# ReuseBlock_Cockcrof_Walton_PCB_2025-01-0.net
KiCad netlist of a schematic drawn in EasyEDA Pro
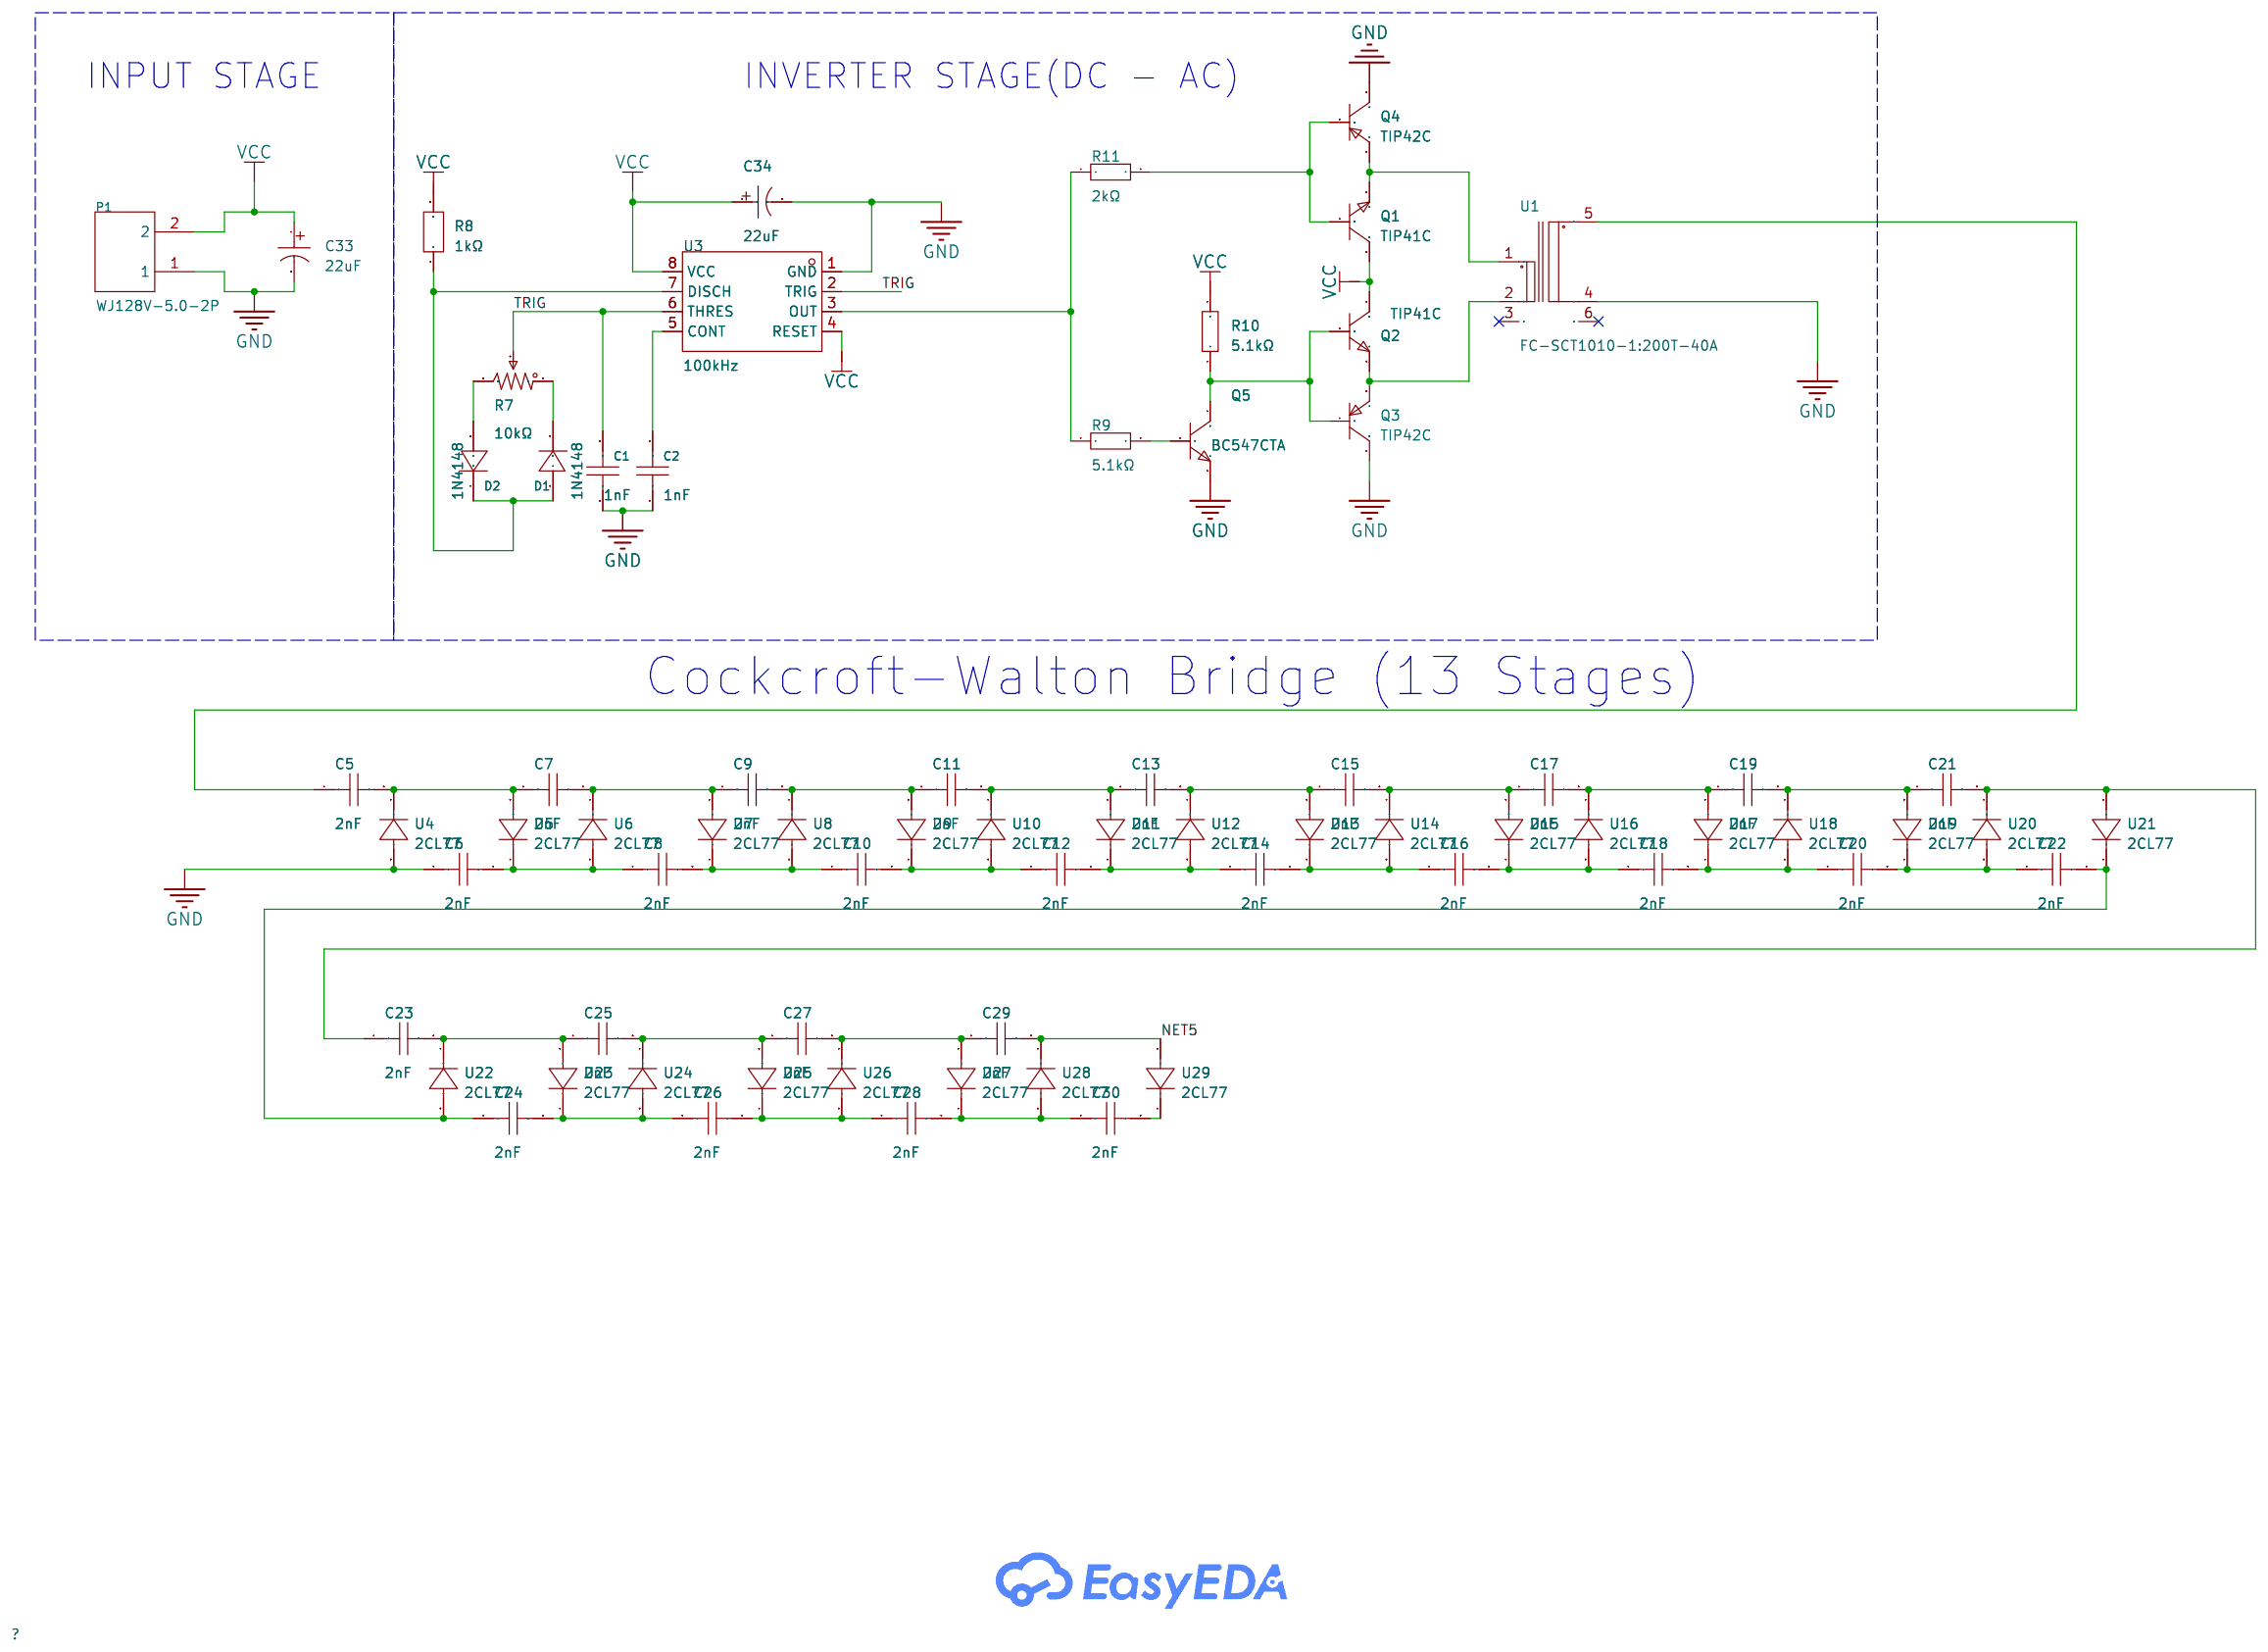
[diagram p0: schematic sheet]

(export (version "E")
  (design (tool "Eeschema 10.0.6"))
  (components
    (comp (ref "C1")
      (value "1nF")
      (footprint "easyedapro:CAP-TH_L8.0-W3.0-P5.0-D0.60")
      (fields (field (name "Manufacturer Part") "R08B1B102KN0B0S0N0") (field (name "Manufacturer") "STE(松田)"))
      (libsource (lib "easyedapro") (part "R08B1B102KN0B0S0N0"))
    )
    (comp (ref "C2")
      (value "1nF")
      (footprint "easyedapro:CAP-TH_L8.0-W3.0-P5.0-D0.60")
      (fields (field (name "Manufacturer Part") "R08B1B102KN0B0S0N0") (field (name "Manufacturer") "STE(松田)"))
      (libsource (lib "easyedapro") (part "R08B1B102KN0B0S0N0"))
    )
    (comp (ref "C5")
      (value "2nF")
      (footprint "easyedapro:CAP-TH_L19.0-W8.0-P12.50-D0.8-S8.0")
      (fields
        (field (name "Manufacturer Part") "HVCC153Y6P202MEAX")
        (field (name "Manufacturer") "VISHAY(威世)")
      )
      (libsource (lib "easyedapro") (part "HVCC153Y6P202MEAX"))
    )
    (comp (ref "C6")
      (value "2nF")
      (footprint "easyedapro:CAP-TH_L19.0-W8.0-P12.50-D0.8-S8.0")
      (fields
        (field (name "Manufacturer Part") "HVCC153Y6P202MEAX")
        (field (name "Manufacturer") "VISHAY(威世)")
      )
      (libsource (lib "easyedapro") (part "HVCC153Y6P202MEAX"))
    )
    (comp (ref "C7")
      (value "2nF")
      (footprint "easyedapro:CAP-TH_L19.0-W8.0-P12.50-D0.8-S8.0")
      (fields
        (field (name "Manufacturer Part") "HVCC153Y6P202MEAX")
        (field (name "Manufacturer") "VISHAY(威世)")
      )
      (libsource (lib "easyedapro") (part "HVCC153Y6P202MEAX"))
    )
    (comp (ref "C8")
      (value "2nF")
      (footprint "easyedapro:CAP-TH_L19.0-W8.0-P12.50-D0.8-S8.0")
      (fields
        (field (name "Manufacturer Part") "HVCC153Y6P202MEAX")
        (field (name "Manufacturer") "VISHAY(威世)")
      )
      (libsource (lib "easyedapro") (part "HVCC153Y6P202MEAX"))
    )
    (comp (ref "C9")
      (value "2nF")
      (footprint "easyedapro:CAP-TH_L19.0-W8.0-P12.50-D0.8-S8.0")
      (fields
        (field (name "Manufacturer Part") "HVCC153Y6P202MEAX")
        (field (name "Manufacturer") "VISHAY(威世)")
      )
      (libsource (lib "easyedapro") (part "HVCC153Y6P202MEAX"))
    )
    (comp (ref "C10")
      (value "2nF")
      (footprint "easyedapro:CAP-TH_L19.0-W8.0-P12.50-D0.8-S8.0")
      (fields
        (field (name "Manufacturer Part") "HVCC153Y6P202MEAX")
        (field (name "Manufacturer") "VISHAY(威世)")
      )
      (libsource (lib "easyedapro") (part "HVCC153Y6P202MEAX"))
    )
    (comp (ref "C11")
      (value "2nF")
      (footprint "easyedapro:CAP-TH_L19.0-W8.0-P12.50-D0.8-S8.0")
      (fields
        (field (name "Manufacturer Part") "HVCC153Y6P202MEAX")
        (field (name "Manufacturer") "VISHAY(威世)")
      )
      (libsource (lib "easyedapro") (part "HVCC153Y6P202MEAX"))
    )
    (comp (ref "C12")
      (value "2nF")
      (footprint "easyedapro:CAP-TH_L19.0-W8.0-P12.50-D0.8-S8.0")
      (fields
        (field (name "Manufacturer Part") "HVCC153Y6P202MEAX")
        (field (name "Manufacturer") "VISHAY(威世)")
      )
      (libsource (lib "easyedapro") (part "HVCC153Y6P202MEAX"))
    )
    (comp (ref "C13")
      (value "2nF")
      (footprint "easyedapro:CAP-TH_L19.0-W8.0-P12.50-D0.8-S8.0")
      (fields
        (field (name "Manufacturer Part") "HVCC153Y6P202MEAX")
        (field (name "Manufacturer") "VISHAY(威世)")
      )
      (libsource (lib "easyedapro") (part "HVCC153Y6P202MEAX"))
    )
    (comp (ref "C14")
      (value "2nF")
      (footprint "easyedapro:CAP-TH_L19.0-W8.0-P12.50-D0.8-S8.0")
      (fields
        (field (name "Manufacturer Part") "HVCC153Y6P202MEAX")
        (field (name "Manufacturer") "VISHAY(威世)")
      )
      (libsource (lib "easyedapro") (part "HVCC153Y6P202MEAX"))
    )
    (comp (ref "C15")
      (value "2nF")
      (footprint "easyedapro:CAP-TH_L19.0-W8.0-P12.50-D0.8-S8.0")
      (fields
        (field (name "Manufacturer Part") "HVCC153Y6P202MEAX")
        (field (name "Manufacturer") "VISHAY(威世)")
      )
      (libsource (lib "easyedapro") (part "HVCC153Y6P202MEAX"))
    )
    (comp (ref "C16")
      (value "2nF")
      (footprint "easyedapro:CAP-TH_L19.0-W8.0-P12.50-D0.8-S8.0")
      (fields
        (field (name "Manufacturer Part") "HVCC153Y6P202MEAX")
        (field (name "Manufacturer") "VISHAY(威世)")
      )
      (libsource (lib "easyedapro") (part "HVCC153Y6P202MEAX"))
    )
    (comp (ref "C17")
      (value "2nF")
      (footprint "easyedapro:CAP-TH_L19.0-W8.0-P12.50-D0.8-S8.0")
      (fields
        (field (name "Manufacturer Part") "HVCC153Y6P202MEAX")
        (field (name "Manufacturer") "VISHAY(威世)")
      )
      (libsource (lib "easyedapro") (part "HVCC153Y6P202MEAX"))
    )
    (comp (ref "C18")
      (value "2nF")
      (footprint "easyedapro:CAP-TH_L19.0-W8.0-P12.50-D0.8-S8.0")
      (fields
        (field (name "Manufacturer Part") "HVCC153Y6P202MEAX")
        (field (name "Manufacturer") "VISHAY(威世)")
      )
      (libsource (lib "easyedapro") (part "HVCC153Y6P202MEAX"))
    )
    (comp (ref "C19")
      (value "2nF")
      (footprint "easyedapro:CAP-TH_L19.0-W8.0-P12.50-D0.8-S8.0")
      (fields
        (field (name "Manufacturer Part") "HVCC153Y6P202MEAX")
        (field (name "Manufacturer") "VISHAY(威世)")
      )
      (libsource (lib "easyedapro") (part "HVCC153Y6P202MEAX"))
    )
    (comp (ref "C20")
      (value "2nF")
      (footprint "easyedapro:CAP-TH_L19.0-W8.0-P12.50-D0.8-S8.0")
      (fields
        (field (name "Manufacturer Part") "HVCC153Y6P202MEAX")
        (field (name "Manufacturer") "VISHAY(威世)")
      )
      (libsource (lib "easyedapro") (part "HVCC153Y6P202MEAX"))
    )
    (comp (ref "C21")
      (value "2nF")
      (footprint "easyedapro:CAP-TH_L19.0-W8.0-P12.50-D0.8-S8.0")
      (fields
        (field (name "Manufacturer Part") "HVCC153Y6P202MEAX")
        (field (name "Manufacturer") "VISHAY(威世)")
      )
      (libsource (lib "easyedapro") (part "HVCC153Y6P202MEAX"))
    )
    (comp (ref "C22")
      (value "2nF")
      (footprint "easyedapro:CAP-TH_L19.0-W8.0-P12.50-D0.8-S8.0")
      (fields
        (field (name "Manufacturer Part") "HVCC153Y6P202MEAX")
        (field (name "Manufacturer") "VISHAY(威世)")
      )
      (libsource (lib "easyedapro") (part "HVCC153Y6P202MEAX"))
    )
    (comp (ref "C23")
      (value "2nF")
      (footprint "easyedapro:CAP-TH_L19.0-W8.0-P12.50-D0.8-S8.0")
      (fields
        (field (name "Manufacturer Part") "HVCC153Y6P202MEAX")
        (field (name "Manufacturer") "VISHAY(威世)")
      )
      (libsource (lib "easyedapro") (part "HVCC153Y6P202MEAX"))
    )
    (comp (ref "C24")
      (value "2nF")
      (footprint "easyedapro:CAP-TH_L19.0-W8.0-P12.50-D0.8-S8.0")
      (fields
        (field (name "Manufacturer Part") "HVCC153Y6P202MEAX")
        (field (name "Manufacturer") "VISHAY(威世)")
      )
      (libsource (lib "easyedapro") (part "HVCC153Y6P202MEAX"))
    )
    (comp (ref "C25")
      (value "2nF")
      (footprint "easyedapro:CAP-TH_L19.0-W8.0-P12.50-D0.8-S8.0")
      (fields
        (field (name "Manufacturer Part") "HVCC153Y6P202MEAX")
        (field (name "Manufacturer") "VISHAY(威世)")
      )
      (libsource (lib "easyedapro") (part "HVCC153Y6P202MEAX"))
    )
    (comp (ref "C26")
      (value "2nF")
      (footprint "easyedapro:CAP-TH_L19.0-W8.0-P12.50-D0.8-S8.0")
      (fields
        (field (name "Manufacturer Part") "HVCC153Y6P202MEAX")
        (field (name "Manufacturer") "VISHAY(威世)")
      )
      (libsource (lib "easyedapro") (part "HVCC153Y6P202MEAX"))
    )
    (comp (ref "C27")
      (value "2nF")
      (footprint "easyedapro:CAP-TH_L19.0-W8.0-P12.50-D0.8-S8.0")
      (fields
        (field (name "Manufacturer Part") "HVCC153Y6P202MEAX")
        (field (name "Manufacturer") "VISHAY(威世)")
      )
      (libsource (lib "easyedapro") (part "HVCC153Y6P202MEAX"))
    )
    (comp (ref "C28")
      (value "2nF")
      (footprint "easyedapro:CAP-TH_L19.0-W8.0-P12.50-D0.8-S8.0")
      (fields
        (field (name "Manufacturer Part") "HVCC153Y6P202MEAX")
        (field (name "Manufacturer") "VISHAY(威世)")
      )
      (libsource (lib "easyedapro") (part "HVCC153Y6P202MEAX"))
    )
    (comp (ref "C29")
      (value "2nF")
      (footprint "easyedapro:CAP-TH_L19.0-W8.0-P12.50-D0.8-S8.0")
      (fields
        (field (name "Manufacturer Part") "HVCC153Y6P202MEAX")
        (field (name "Manufacturer") "VISHAY(威世)")
      )
      (libsource (lib "easyedapro") (part "HVCC153Y6P202MEAX"))
    )
    (comp (ref "C30")
      (value "2nF")
      (footprint "easyedapro:CAP-TH_L19.0-W8.0-P12.50-D0.8-S8.0")
      (fields
        (field (name "Manufacturer Part") "HVCC153Y6P202MEAX")
        (field (name "Manufacturer") "VISHAY(威世)")
      )
      (libsource (lib "easyedapro") (part "HVCC153Y6P202MEAX"))
    )
    (comp (ref "C33")
      (value "22uF")
      (footprint "easyedapro:CAP-TH_BD5.0-P2.00-D0.8-FD")
      (fields
        (field (name "Manufacturer Part") "GR226M050D11RR0VH4FP0")
        (field (name "Manufacturer") "CX(承兴)")
      )
      (libsource (lib "easyedapro") (part "22UF 50V高频低阻"))
    )
    (comp (ref "C34")
      (value "22uF")
      (footprint "easyedapro:CAP-TH_BD5.0-P2.00-D0.8-FD")
      (fields
        (field (name "Manufacturer Part") "GR226M050D11RR0VH4FP0")
        (field (name "Manufacturer") "CX(承兴)")
      )
      (libsource (lib "easyedapro") (part "22UF 50V高频低阻"))
    )
    (comp (ref "D1")
      (value "1N4148")
      (footprint "easyedapro:DO-35_BD2.0-L4.2-P8.20-D0.5-RD")
      (fields (field (name "Manufacturer") "LGE(鲁光)"))
      (libsource (lib "easyedapro") (part "1N4148_C402212"))
    )
    (comp (ref "D2")
      (value "1N4148")
      (footprint "easyedapro:DO-35_BD2.0-L4.2-P8.20-D0.5-RD")
      (fields (field (name "Manufacturer") "LGE(鲁光)"))
      (libsource (lib "easyedapro") (part "1N4148_C402212"))
    )
    (comp (ref "P1")
      (value "WJ128V-5.0-2P")
      (footprint "easyedapro:CONN-TH_2P-P5.00_WJ128V-5.0-2P")
      (fields (field (name "Manufacturer") "KANGNEX(康奈克斯电气)"))
      (libsource (lib "easyedapro") (part "WJ128V-5.0-2P"))
    )
    (comp (ref "Q1")
      (value "TIP41C")
      (footprint "easyedapro:TO-220-3_L10.0-W4.5-P2.54-T")
      (fields (field (name "Manufacturer") "CJ(江苏长电/长晶)"))
      (libsource (lib "easyedapro") (part "TIP41C"))
    )
    (comp (ref "Q2")
      (value "TIP41C")
      (footprint "easyedapro:TO-220-3_L10.0-W4.5-P2.54-T")
      (fields (field (name "Manufacturer") "CJ(江苏长电/长晶)"))
      (libsource (lib "easyedapro") (part "TIP41C"))
    )
    (comp (ref "Q3")
      (value "TIP42C")
      (footprint "easyedapro:ITO-220AB-3_L10.2-W4.5-P2.60-L")
      (fields (field (name "Manufacturer") "ST(意法半导体)"))
      (libsource (lib "easyedapro") (part "TIP42C_C410524"))
    )
    (comp (ref "Q4")
      (value "TIP42C")
      (footprint "easyedapro:ITO-220AB-3_L10.2-W4.5-P2.60-L")
      (fields (field (name "Manufacturer") "ST(意法半导体)"))
      (libsource (lib "easyedapro") (part "TIP42C_C410524"))
    )
    (comp (ref "Q5")
      (value "BC547CTA")
      (footprint "easyedapro:TO-92-3_L4.8-W3.7-P2.54-L")
      (fields (field (name "Manufacturer") "onsemi(安森美)"))
      (libsource (lib "easyedapro") (part "BC547CTA"))
    )
    (comp (ref "R7")
      (value "10kΩ")
      (footprint "easyedapro:RES-ADJ-TH_3P-L10.0-W10.0-P2.50-L")
      (description "Resistance: Tolerance:±10% Tolerance:±10%")
      (fields (field (name "Manufacturer Part") "3296W-1-103") (field (name "Manufacturer") "BOCHEN(博晨)"))
      (libsource (lib "easyedapro") (part "3296W-1-103"))
    )
    (comp (ref "R8")
      (value "1kΩ")
      (footprint "easyedapro:RES-TH_BD2.3-L6.5-P10.50-D0.5")
      (fields (field (name "Manufacturer Part") "MF1/4W-1KΩ±1%T52") (field (name "Manufacturer") "华星机电"))
      (libsource (lib "easyedapro") (part "MF1/4W-1KΩ±1%T52"))
    )
    (comp (ref "R9")
      (value "5.1kΩ")
      (footprint "easyedapro:RES-TH_BD2.2-L6.5-P10.50-D0.6")
      (fields
        (field (name "Manufacturer Part") "CFR0W4J0512A50")
        (field (name "Manufacturer") "UNI-ROYAL(厚声)")
      )
      (libsource (lib "easyedapro") (part "CFR0W4J0512A50"))
    )
    (comp (ref "R10")
      (value "5.1kΩ")
      (footprint "easyedapro:RES-TH_BD2.2-L6.5-P10.50-D0.6")
      (fields
        (field (name "Manufacturer Part") "CFR0W4J0512A50")
        (field (name "Manufacturer") "UNI-ROYAL(厚声)")
      )
      (libsource (lib "easyedapro") (part "CFR0W4J0512A50"))
    )
    (comp (ref "R11")
      (value "2kΩ")
      (footprint "easyedapro:RES-TH_BD2.2-L6.5-P10.50-D0.6")
      (fields
        (field (name "Manufacturer Part") "MFR0W4F2001A50")
        (field (name "Manufacturer") "UNI-ROYAL(厚声)")
      )
      (libsource (lib "easyedapro") (part "MFR0W4F2001A50"))
    )
    (comp (ref "U1")
      (value "FC-SCT1010-1:200T-40A")
      (footprint "easyedapro:XFMR-SMD_6P-P2.50_FC-SCT1010")
      (description "Current Ratio:1:200 Current Rating:40A")
      (fields (field (name "Manufacturer") "FC(方成)"))
      (libsource (lib "easyedapro") (part "FC-SCT1010-1{colon}200T-40A"))
    )
    (comp (ref "U3")
      (value "100kHz")
      (footprint "easyedapro:DIP-8_L9.8-W6.6-P2.54-LS7.6-BL")
      (fields (field (name "Manufacturer Part") "NE555P") (field (name "Manufacturer") "TI(德州仪器)"))
      (libsource (lib "easyedapro") (part "NE555P"))
    )
    (comp (ref "U4")
      (value "2CL77")
      (footprint "easyedapro:DIO-TH_BD3.0-L12.0-P16.00-D0.6")
      (description "Reverse Voltage (Vr): Average Rectified Current (Io): Reverse Leakage Current:2uA")
      (fields (field (name "Manufacturer") "SUNMATE(森美特)"))
      (libsource (lib "easyedapro") (part "2CL77"))
    )
    (comp (ref "U5")
      (value "2CL77")
      (footprint "easyedapro:DIO-TH_BD3.0-L12.0-P16.00-D0.6")
      (description "Reverse Voltage (Vr): Average Rectified Current (Io): Reverse Leakage Current:2uA")
      (fields (field (name "Manufacturer") "SUNMATE(森美特)"))
      (libsource (lib "easyedapro") (part "2CL77"))
    )
    (comp (ref "U6")
      (value "2CL77")
      (footprint "easyedapro:DIO-TH_BD3.0-L12.0-P16.00-D0.6")
      (description "Reverse Voltage (Vr): Average Rectified Current (Io): Reverse Leakage Current:2uA")
      (fields (field (name "Manufacturer") "SUNMATE(森美特)"))
      (libsource (lib "easyedapro") (part "2CL77"))
    )
    (comp (ref "U7")
      (value "2CL77")
      (footprint "easyedapro:DIO-TH_BD3.0-L12.0-P16.00-D0.6")
      (description "Reverse Voltage (Vr): Average Rectified Current (Io): Reverse Leakage Current:2uA")
      (fields (field (name "Manufacturer") "SUNMATE(森美特)"))
      (libsource (lib "easyedapro") (part "2CL77"))
    )
    (comp (ref "U8")
      (value "2CL77")
      (footprint "easyedapro:DIO-TH_BD3.0-L12.0-P16.00-D0.6")
      (description "Reverse Voltage (Vr): Average Rectified Current (Io): Reverse Leakage Current:2uA")
      (fields (field (name "Manufacturer") "SUNMATE(森美特)"))
      (libsource (lib "easyedapro") (part "2CL77"))
    )
    (comp (ref "U9")
      (value "2CL77")
      (footprint "easyedapro:DIO-TH_BD3.0-L12.0-P16.00-D0.6")
      (description "Reverse Voltage (Vr): Average Rectified Current (Io): Reverse Leakage Current:2uA")
      (fields (field (name "Manufacturer") "SUNMATE(森美特)"))
      (libsource (lib "easyedapro") (part "2CL77"))
    )
    (comp (ref "U10")
      (value "2CL77")
      (footprint "easyedapro:DIO-TH_BD3.0-L12.0-P16.00-D0.6")
      (description "Reverse Voltage (Vr): Average Rectified Current (Io): Reverse Leakage Current:2uA")
      (fields (field (name "Manufacturer") "SUNMATE(森美特)"))
      (libsource (lib "easyedapro") (part "2CL77"))
    )
    (comp (ref "U11")
      (value "2CL77")
      (footprint "easyedapro:DIO-TH_BD3.0-L12.0-P16.00-D0.6")
      (description "Reverse Voltage (Vr): Average Rectified Current (Io): Reverse Leakage Current:2uA")
      (fields (field (name "Manufacturer") "SUNMATE(森美特)"))
      (libsource (lib "easyedapro") (part "2CL77"))
    )
    (comp (ref "U12")
      (value "2CL77")
      (footprint "easyedapro:DIO-TH_BD3.0-L12.0-P16.00-D0.6")
      (description "Reverse Voltage (Vr): Average Rectified Current (Io): Reverse Leakage Current:2uA")
      (fields (field (name "Manufacturer") "SUNMATE(森美特)"))
      (libsource (lib "easyedapro") (part "2CL77"))
    )
    (comp (ref "U13")
      (value "2CL77")
      (footprint "easyedapro:DIO-TH_BD3.0-L12.0-P16.00-D0.6")
      (description "Reverse Voltage (Vr): Average Rectified Current (Io): Reverse Leakage Current:2uA")
      (fields (field (name "Manufacturer") "SUNMATE(森美特)"))
      (libsource (lib "easyedapro") (part "2CL77"))
    )
    (comp (ref "U14")
      (value "2CL77")
      (footprint "easyedapro:DIO-TH_BD3.0-L12.0-P16.00-D0.6")
      (description "Reverse Voltage (Vr): Average Rectified Current (Io): Reverse Leakage Current:2uA")
      (fields (field (name "Manufacturer") "SUNMATE(森美特)"))
      (libsource (lib "easyedapro") (part "2CL77"))
    )
    (comp (ref "U15")
      (value "2CL77")
      (footprint "easyedapro:DIO-TH_BD3.0-L12.0-P16.00-D0.6")
      (description "Reverse Voltage (Vr): Average Rectified Current (Io): Reverse Leakage Current:2uA")
      (fields (field (name "Manufacturer") "SUNMATE(森美特)"))
      (libsource (lib "easyedapro") (part "2CL77"))
    )
    (comp (ref "U16")
      (value "2CL77")
      (footprint "easyedapro:DIO-TH_BD3.0-L12.0-P16.00-D0.6")
      (description "Reverse Voltage (Vr): Average Rectified Current (Io): Reverse Leakage Current:2uA")
      (fields (field (name "Manufacturer") "SUNMATE(森美特)"))
      (libsource (lib "easyedapro") (part "2CL77"))
    )
    (comp (ref "U17")
      (value "2CL77")
      (footprint "easyedapro:DIO-TH_BD3.0-L12.0-P16.00-D0.6")
      (description "Reverse Voltage (Vr): Average Rectified Current (Io): Reverse Leakage Current:2uA")
      (fields (field (name "Manufacturer") "SUNMATE(森美特)"))
      (libsource (lib "easyedapro") (part "2CL77"))
    )
    (comp (ref "U18")
      (value "2CL77")
      (footprint "easyedapro:DIO-TH_BD3.0-L12.0-P16.00-D0.6")
      (description "Reverse Voltage (Vr): Average Rectified Current (Io): Reverse Leakage Current:2uA")
      (fields (field (name "Manufacturer") "SUNMATE(森美特)"))
      (libsource (lib "easyedapro") (part "2CL77"))
    )
    (comp (ref "U19")
      (value "2CL77")
      (footprint "easyedapro:DIO-TH_BD3.0-L12.0-P16.00-D0.6")
      (description "Reverse Voltage (Vr): Average Rectified Current (Io): Reverse Leakage Current:2uA")
      (fields (field (name "Manufacturer") "SUNMATE(森美特)"))
      (libsource (lib "easyedapro") (part "2CL77"))
    )
    (comp (ref "U20")
      (value "2CL77")
      (footprint "easyedapro:DIO-TH_BD3.0-L12.0-P16.00-D0.6")
      (description "Reverse Voltage (Vr): Average Rectified Current (Io): Reverse Leakage Current:2uA")
      (fields (field (name "Manufacturer") "SUNMATE(森美特)"))
      (libsource (lib "easyedapro") (part "2CL77"))
    )
    (comp (ref "U21")
      (value "2CL77")
      (footprint "easyedapro:DIO-TH_BD3.0-L12.0-P16.00-D0.6")
      (description "Reverse Voltage (Vr): Average Rectified Current (Io): Reverse Leakage Current:2uA")
      (fields (field (name "Manufacturer") "SUNMATE(森美特)"))
      (libsource (lib "easyedapro") (part "2CL77"))
    )
    (comp (ref "U22")
      (value "2CL77")
      (footprint "easyedapro:DIO-TH_BD3.0-L12.0-P16.00-D0.6")
      (description "Reverse Voltage (Vr): Average Rectified Current (Io): Reverse Leakage Current:2uA")
      (fields (field (name "Manufacturer") "SUNMATE(森美特)"))
      (libsource (lib "easyedapro") (part "2CL77"))
    )
    (comp (ref "U23")
      (value "2CL77")
      (footprint "easyedapro:DIO-TH_BD3.0-L12.0-P16.00-D0.6")
      (description "Reverse Voltage (Vr): Average Rectified Current (Io): Reverse Leakage Current:2uA")
      (fields (field (name "Manufacturer") "SUNMATE(森美特)"))
      (libsource (lib "easyedapro") (part "2CL77"))
    )
    (comp (ref "U24")
      (value "2CL77")
      (footprint "easyedapro:DIO-TH_BD3.0-L12.0-P16.00-D0.6")
      (description "Reverse Voltage (Vr): Average Rectified Current (Io): Reverse Leakage Current:2uA")
      (fields (field (name "Manufacturer") "SUNMATE(森美特)"))
      (libsource (lib "easyedapro") (part "2CL77"))
    )
    (comp (ref "U25")
      (value "2CL77")
      (footprint "easyedapro:DIO-TH_BD3.0-L12.0-P16.00-D0.6")
      (description "Reverse Voltage (Vr): Average Rectified Current (Io): Reverse Leakage Current:2uA")
      (fields (field (name "Manufacturer") "SUNMATE(森美特)"))
      (libsource (lib "easyedapro") (part "2CL77"))
    )
    (comp (ref "U26")
      (value "2CL77")
      (footprint "easyedapro:DIO-TH_BD3.0-L12.0-P16.00-D0.6")
      (description "Reverse Voltage (Vr): Average Rectified Current (Io): Reverse Leakage Current:2uA")
      (fields (field (name "Manufacturer") "SUNMATE(森美特)"))
      (libsource (lib "easyedapro") (part "2CL77"))
    )
    (comp (ref "U27")
      (value "2CL77")
      (footprint "easyedapro:DIO-TH_BD3.0-L12.0-P16.00-D0.6")
      (description "Reverse Voltage (Vr): Average Rectified Current (Io): Reverse Leakage Current:2uA")
      (fields (field (name "Manufacturer") "SUNMATE(森美特)"))
      (libsource (lib "easyedapro") (part "2CL77"))
    )
    (comp (ref "U28")
      (value "2CL77")
      (footprint "easyedapro:DIO-TH_BD3.0-L12.0-P16.00-D0.6")
      (description "Reverse Voltage (Vr): Average Rectified Current (Io): Reverse Leakage Current:2uA")
      (fields (field (name "Manufacturer") "SUNMATE(森美特)"))
      (libsource (lib "easyedapro") (part "2CL77"))
    )
    (comp (ref "U29")
      (value "2CL77")
      (footprint "easyedapro:DIO-TH_BD3.0-L12.0-P16.00-D0.6")
      (description "Reverse Voltage (Vr): Average Rectified Current (Io): Reverse Leakage Current:2uA")
      (fields (field (name "Manufacturer") "SUNMATE(森美特)"))
      (libsource (lib "easyedapro") (part "2CL77"))
    )
  )
  (nets
    (net (code "1") (name "/NET5") (class "Default")
      (node (ref "C29") (pin "2") (pinfunction "2_2") (pintype "unspecified"))
      (node (ref "U28") (pin "1") (pinfunction "K_1") (pintype "unspecified"))
      (node (ref "U29") (pin "2") (pinfunction "A_2") (pintype "unspecified"))
    )
    (net (code "2") (name "/TRIG") (class "Default")
      (node (ref "C1") (pin "2") (pinfunction "2_2") (pintype "input"))
      (node (ref "R7") (pin "2") (pinfunction "2_2") (pintype "input"))
      (node (ref "U3") (pin "2") (pinfunction "TRIG_2") (pintype "input"))
      (node (ref "U3") (pin "6") (pinfunction "THRES_6") (pintype "input"))
    )
    (net (code "3") (name "GND") (class "Default")
      (node (ref "C1") (pin "1") (pinfunction "1_1") (pintype "input"))
      (node (ref "C2") (pin "1") (pinfunction "1_1") (pintype "input"))
      (node (ref "C33") (pin "2") (pinfunction "2_2") (pintype "input"))
      (node (ref "C34") (pin "2") (pinfunction "2_2") (pintype "input"))
      (node (ref "C6") (pin "1") (pinfunction "1_1") (pintype "unspecified"))
      (node (ref "P1") (pin "1") (pinfunction "1_1") (pintype "input"))
      (node (ref "Q3") (pin "2") (pinfunction "C_2") (pintype "unspecified"))
      (node (ref "Q4") (pin "2") (pinfunction "C_2") (pintype "unspecified"))
      (node (ref "Q5") (pin "3") (pinfunction "E_3") (pintype "input"))
      (node (ref "U1") (pin "4") (pinfunction "4_4") (pintype "unspecified"))
      (node (ref "U3") (pin "1") (pinfunction "GND_1") (pintype "input"))
      (node (ref "U4") (pin "2") (pinfunction "A_2") (pintype "unspecified"))
    )
    (net (code "4") (name "Net-(C5-Pad1)") (class "Default")
      (node (ref "C5") (pin "1") (pinfunction "1_1") (pintype "unspecified"))
      (node (ref "U1") (pin "5") (pinfunction "5_5") (pintype "unspecified"))
    )
    (net (code "5") (name "Net-(D1-A)") (class "Default")
      (node (ref "D1") (pin "2") (pinfunction "A_2") (pintype "input"))
      (node (ref "D2") (pin "1") (pinfunction "C_1") (pintype "input"))
      (node (ref "R8") (pin "1") (pinfunction "1_1") (pintype "unspecified"))
      (node (ref "U3") (pin "7") (pinfunction "DISCH_7") (pintype "input"))
    )
    (net (code "6") (name "Net-(D1-C)") (class "Default")
      (node (ref "D1") (pin "1") (pinfunction "C_1") (pintype "input"))
      (node (ref "R7") (pin "1") (pinfunction "1_1") (pintype "input"))
    )
    (net (code "7") (name "Net-(D2-A)") (class "Default")
      (node (ref "D2") (pin "2") (pinfunction "A_2") (pintype "input"))
      (node (ref "R7") (pin "3") (pinfunction "3_3") (pintype "input"))
    )
    (net (code "8") (name "Net-(Q1-B)") (class "Default")
      (node (ref "Q1") (pin "1") (pinfunction "B_1") (pintype "unspecified"))
      (node (ref "Q4") (pin "1") (pinfunction "B_1") (pintype "unspecified"))
      (node (ref "R11") (pin "2") (pinfunction "2_2") (pintype "input"))
    )
    (net (code "9") (name "Net-(Q1-E)") (class "Default")
      (node (ref "Q1") (pin "3") (pinfunction "E_3") (pintype "unspecified"))
      (node (ref "Q4") (pin "3") (pinfunction "E_3") (pintype "unspecified"))
      (node (ref "U1") (pin "1") (pinfunction "1_1") (pintype "unspecified"))
    )
    (net (code "10") (name "Net-(Q2-B)") (class "Default")
      (node (ref "Q2") (pin "1") (pinfunction "B_1") (pintype "unspecified"))
      (node (ref "Q3") (pin "1") (pinfunction "B_1") (pintype "unspecified"))
      (node (ref "Q5") (pin "1") (pinfunction "C_1") (pintype "input"))
      (node (ref "R10") (pin "1") (pinfunction "1_1") (pintype "input"))
    )
    (net (code "11") (name "Net-(Q2-E)") (class "Default")
      (node (ref "Q2") (pin "3") (pinfunction "E_3") (pintype "unspecified"))
      (node (ref "Q3") (pin "3") (pinfunction "E_3") (pintype "unspecified"))
      (node (ref "U1") (pin "2") (pinfunction "2_2") (pintype "unspecified"))
    )
    (net (code "12") (name "Net-(Q5-B)") (class "Default")
      (node (ref "Q5") (pin "2") (pinfunction "B_2") (pintype "input"))
      (node (ref "R9") (pin "2") (pinfunction "2_2") (pintype "input"))
    )
    (net (code "13") (name "Net-(U3-CONT)") (class "Default")
      (node (ref "C2") (pin "2") (pinfunction "2_2") (pintype "input"))
      (node (ref "U3") (pin "5") (pinfunction "CONT_5") (pintype "input"))
    )
    (net (code "14") (name "Net-(U3-OUT)") (class "Default")
      (node (ref "R11") (pin "1") (pinfunction "1_1") (pintype "input"))
      (node (ref "R9") (pin "1") (pinfunction "1_1") (pintype "input"))
      (node (ref "U3") (pin "3") (pinfunction "OUT_3") (pintype "input"))
    )
    (net (code "15") (name "Net-(U4-K)") (class "Default")
      (node (ref "C5") (pin "2") (pinfunction "2_2") (pintype "unspecified"))
      (node (ref "C7") (pin "1") (pinfunction "1_1") (pintype "unspecified"))
      (node (ref "U4") (pin "1") (pinfunction "K_1") (pintype "unspecified"))
      (node (ref "U5") (pin "2") (pinfunction "A_2") (pintype "unspecified"))
    )
    (net (code "16") (name "Net-(U5-K)") (class "Default")
      (node (ref "C6") (pin "2") (pinfunction "2_2") (pintype "unspecified"))
      (node (ref "C8") (pin "1") (pinfunction "1_1") (pintype "unspecified"))
      (node (ref "U5") (pin "1") (pinfunction "K_1") (pintype "unspecified"))
      (node (ref "U6") (pin "2") (pinfunction "A_2") (pintype "unspecified"))
    )
    (net (code "17") (name "Net-(U6-K)") (class "Default")
      (node (ref "C7") (pin "2") (pinfunction "2_2") (pintype "unspecified"))
      (node (ref "C9") (pin "1") (pinfunction "1_1") (pintype "unspecified"))
      (node (ref "U6") (pin "1") (pinfunction "K_1") (pintype "unspecified"))
      (node (ref "U7") (pin "2") (pinfunction "A_2") (pintype "unspecified"))
    )
    (net (code "18") (name "Net-(U7-K)") (class "Default")
      (node (ref "C10") (pin "1") (pinfunction "1_1") (pintype "unspecified"))
      (node (ref "C8") (pin "2") (pinfunction "2_2") (pintype "unspecified"))
      (node (ref "U7") (pin "1") (pinfunction "K_1") (pintype "unspecified"))
      (node (ref "U8") (pin "2") (pinfunction "A_2") (pintype "unspecified"))
    )
    (net (code "19") (name "Net-(U8-K)") (class "Default")
      (node (ref "C11") (pin "1") (pinfunction "1_1") (pintype "unspecified"))
      (node (ref "C9") (pin "2") (pinfunction "2_2") (pintype "unspecified"))
      (node (ref "U8") (pin "1") (pinfunction "K_1") (pintype "unspecified"))
      (node (ref "U9") (pin "2") (pinfunction "A_2") (pintype "unspecified"))
    )
    (net (code "20") (name "Net-(U10-A)") (class "Default")
      (node (ref "C10") (pin "2") (pinfunction "2_2") (pintype "unspecified"))
      (node (ref "C12") (pin "1") (pinfunction "1_1") (pintype "unspecified"))
      (node (ref "U10") (pin "2") (pinfunction "A_2") (pintype "unspecified"))
      (node (ref "U9") (pin "1") (pinfunction "K_1") (pintype "unspecified"))
    )
    (net (code "21") (name "Net-(U10-K)") (class "Default")
      (node (ref "C11") (pin "2") (pinfunction "2_2") (pintype "unspecified"))
      (node (ref "C13") (pin "1") (pinfunction "1_1") (pintype "unspecified"))
      (node (ref "U10") (pin "1") (pinfunction "K_1") (pintype "unspecified"))
      (node (ref "U11") (pin "2") (pinfunction "A_2") (pintype "unspecified"))
    )
    (net (code "22") (name "Net-(U11-K)") (class "Default")
      (node (ref "C12") (pin "2") (pinfunction "2_2") (pintype "unspecified"))
      (node (ref "C14") (pin "1") (pinfunction "1_1") (pintype "unspecified"))
      (node (ref "U11") (pin "1") (pinfunction "K_1") (pintype "unspecified"))
      (node (ref "U12") (pin "2") (pinfunction "A_2") (pintype "unspecified"))
    )
    (net (code "23") (name "Net-(U12-K)") (class "Default")
      (node (ref "C13") (pin "2") (pinfunction "2_2") (pintype "unspecified"))
      (node (ref "C15") (pin "1") (pinfunction "1_1") (pintype "unspecified"))
      (node (ref "U12") (pin "1") (pinfunction "K_1") (pintype "unspecified"))
      (node (ref "U13") (pin "2") (pinfunction "A_2") (pintype "unspecified"))
    )
    (net (code "24") (name "Net-(U13-K)") (class "Default")
      (node (ref "C14") (pin "2") (pinfunction "2_2") (pintype "unspecified"))
      (node (ref "C16") (pin "1") (pinfunction "1_1") (pintype "unspecified"))
      (node (ref "U13") (pin "1") (pinfunction "K_1") (pintype "unspecified"))
      (node (ref "U14") (pin "2") (pinfunction "A_2") (pintype "unspecified"))
    )
    (net (code "25") (name "Net-(U14-K)") (class "Default")
      (node (ref "C15") (pin "2") (pinfunction "2_2") (pintype "unspecified"))
      (node (ref "C17") (pin "1") (pinfunction "1_1") (pintype "unspecified"))
      (node (ref "U14") (pin "1") (pinfunction "K_1") (pintype "unspecified"))
      (node (ref "U15") (pin "2") (pinfunction "A_2") (pintype "unspecified"))
    )
    (net (code "26") (name "Net-(U15-K)") (class "Default")
      (node (ref "C16") (pin "2") (pinfunction "2_2") (pintype "unspecified"))
      (node (ref "C18") (pin "1") (pinfunction "1_1") (pintype "unspecified"))
      (node (ref "U15") (pin "1") (pinfunction "K_1") (pintype "unspecified"))
      (node (ref "U16") (pin "2") (pinfunction "A_2") (pintype "unspecified"))
    )
    (net (code "27") (name "Net-(U16-K)") (class "Default")
      (node (ref "C17") (pin "2") (pinfunction "2_2") (pintype "unspecified"))
      (node (ref "C19") (pin "1") (pinfunction "1_1") (pintype "unspecified"))
      (node (ref "U16") (pin "1") (pinfunction "K_1") (pintype "unspecified"))
      (node (ref "U17") (pin "2") (pinfunction "A_2") (pintype "unspecified"))
    )
    (net (code "28") (name "Net-(U17-K)") (class "Default")
      (node (ref "C18") (pin "2") (pinfunction "2_2") (pintype "unspecified"))
      (node (ref "C20") (pin "1") (pinfunction "1_1") (pintype "unspecified"))
      (node (ref "U17") (pin "1") (pinfunction "K_1") (pintype "unspecified"))
      (node (ref "U18") (pin "2") (pinfunction "A_2") (pintype "unspecified"))
    )
    (net (code "29") (name "Net-(U18-K)") (class "Default")
      (node (ref "C19") (pin "2") (pinfunction "2_2") (pintype "unspecified"))
      (node (ref "C21") (pin "1") (pinfunction "1_1") (pintype "unspecified"))
      (node (ref "U18") (pin "1") (pinfunction "K_1") (pintype "unspecified"))
      (node (ref "U19") (pin "2") (pinfunction "A_2") (pintype "unspecified"))
    )
    (net (code "30") (name "Net-(U19-K)") (class "Default")
      (node (ref "C20") (pin "2") (pinfunction "2_2") (pintype "unspecified"))
      (node (ref "C22") (pin "1") (pinfunction "1_1") (pintype "unspecified"))
      (node (ref "U19") (pin "1") (pinfunction "K_1") (pintype "unspecified"))
      (node (ref "U20") (pin "2") (pinfunction "A_2") (pintype "unspecified"))
    )
    (net (code "31") (name "Net-(U20-K)") (class "Default")
      (node (ref "C21") (pin "2") (pinfunction "2_2") (pintype "unspecified"))
      (node (ref "C23") (pin "1") (pinfunction "1_1") (pintype "unspecified"))
      (node (ref "U20") (pin "1") (pinfunction "K_1") (pintype "unspecified"))
      (node (ref "U21") (pin "2") (pinfunction "A_2") (pintype "unspecified"))
    )
    (net (code "32") (name "Net-(U21-K)") (class "Default")
      (node (ref "C22") (pin "2") (pinfunction "2_2") (pintype "unspecified"))
      (node (ref "C24") (pin "1") (pinfunction "1_1") (pintype "unspecified"))
      (node (ref "U21") (pin "1") (pinfunction "K_1") (pintype "unspecified"))
      (node (ref "U22") (pin "2") (pinfunction "A_2") (pintype "unspecified"))
    )
    (net (code "33") (name "Net-(U22-K)") (class "Default")
      (node (ref "C23") (pin "2") (pinfunction "2_2") (pintype "unspecified"))
      (node (ref "C25") (pin "1") (pinfunction "1_1") (pintype "unspecified"))
      (node (ref "U22") (pin "1") (pinfunction "K_1") (pintype "unspecified"))
      (node (ref "U23") (pin "2") (pinfunction "A_2") (pintype "unspecified"))
    )
    (net (code "34") (name "Net-(U23-K)") (class "Default")
      (node (ref "C24") (pin "2") (pinfunction "2_2") (pintype "unspecified"))
      (node (ref "C26") (pin "1") (pinfunction "1_1") (pintype "unspecified"))
      (node (ref "U23") (pin "1") (pinfunction "K_1") (pintype "unspecified"))
      (node (ref "U24") (pin "2") (pinfunction "A_2") (pintype "unspecified"))
    )
    (net (code "35") (name "Net-(U24-K)") (class "Default")
      (node (ref "C25") (pin "2") (pinfunction "2_2") (pintype "unspecified"))
      (node (ref "C27") (pin "1") (pinfunction "1_1") (pintype "unspecified"))
      (node (ref "U24") (pin "1") (pinfunction "K_1") (pintype "unspecified"))
      (node (ref "U25") (pin "2") (pinfunction "A_2") (pintype "unspecified"))
    )
    (net (code "36") (name "Net-(U25-K)") (class "Default")
      (node (ref "C26") (pin "2") (pinfunction "2_2") (pintype "unspecified"))
      (node (ref "C28") (pin "1") (pinfunction "1_1") (pintype "unspecified"))
      (node (ref "U25") (pin "1") (pinfunction "K_1") (pintype "unspecified"))
      (node (ref "U26") (pin "2") (pinfunction "A_2") (pintype "unspecified"))
    )
    (net (code "37") (name "Net-(U26-K)") (class "Default")
      (node (ref "C27") (pin "2") (pinfunction "2_2") (pintype "unspecified"))
      (node (ref "C29") (pin "1") (pinfunction "1_1") (pintype "unspecified"))
      (node (ref "U26") (pin "1") (pinfunction "K_1") (pintype "unspecified"))
      (node (ref "U27") (pin "2") (pinfunction "A_2") (pintype "unspecified"))
    )
    (net (code "38") (name "Net-(U27-K)") (class "Default")
      (node (ref "C28") (pin "2") (pinfunction "2_2") (pintype "unspecified"))
      (node (ref "C30") (pin "1") (pinfunction "1_1") (pintype "unspecified"))
      (node (ref "U27") (pin "1") (pinfunction "K_1") (pintype "unspecified"))
      (node (ref "U28") (pin "2") (pinfunction "A_2") (pintype "unspecified"))
    )
    (net (code "39") (name "Net-(U29-K)") (class "Default")
      (node (ref "C30") (pin "2") (pinfunction "2_2") (pintype "unspecified"))
      (node (ref "U29") (pin "1") (pinfunction "K_1") (pintype "unspecified"))
    )
    (net (code "40") (name "VCC") (class "Default")
      (node (ref "C33") (pin "1") (pinfunction "1_1") (pintype "input"))
      (node (ref "C34") (pin "1") (pinfunction "1_1") (pintype "input"))
      (node (ref "P1") (pin "2") (pinfunction "2_2") (pintype "input"))
      (node (ref "Q1") (pin "2") (pinfunction "C_2") (pintype "unspecified"))
      (node (ref "Q2") (pin "2") (pinfunction "C_2") (pintype "unspecified"))
      (node (ref "R10") (pin "2") (pinfunction "2_2") (pintype "input"))
      (node (ref "R8") (pin "2") (pinfunction "2_2") (pintype "unspecified"))
      (node (ref "U3") (pin "4") (pinfunction "RESET_4") (pintype "input"))
      (node (ref "U3") (pin "8") (pinfunction "VCC_8") (pintype "input"))
    )
    (net (code "41") (name "unconnected-(U1-Pad3)") (class "Default")
      (node (ref "U1") (pin "3") (pinfunction "3_3") (pintype "unspecified+no_connect"))
    )
    (net (code "42") (name "unconnected-(U1-Pad6)") (class "Default")
      (node (ref "U1") (pin "6") (pinfunction "6_6") (pintype "unspecified+no_connect"))
    )
  )
)
